# SparkFun_LilyPad-Switched-Battery.net
KiCad netlist of a schematic drawn in EAGLE
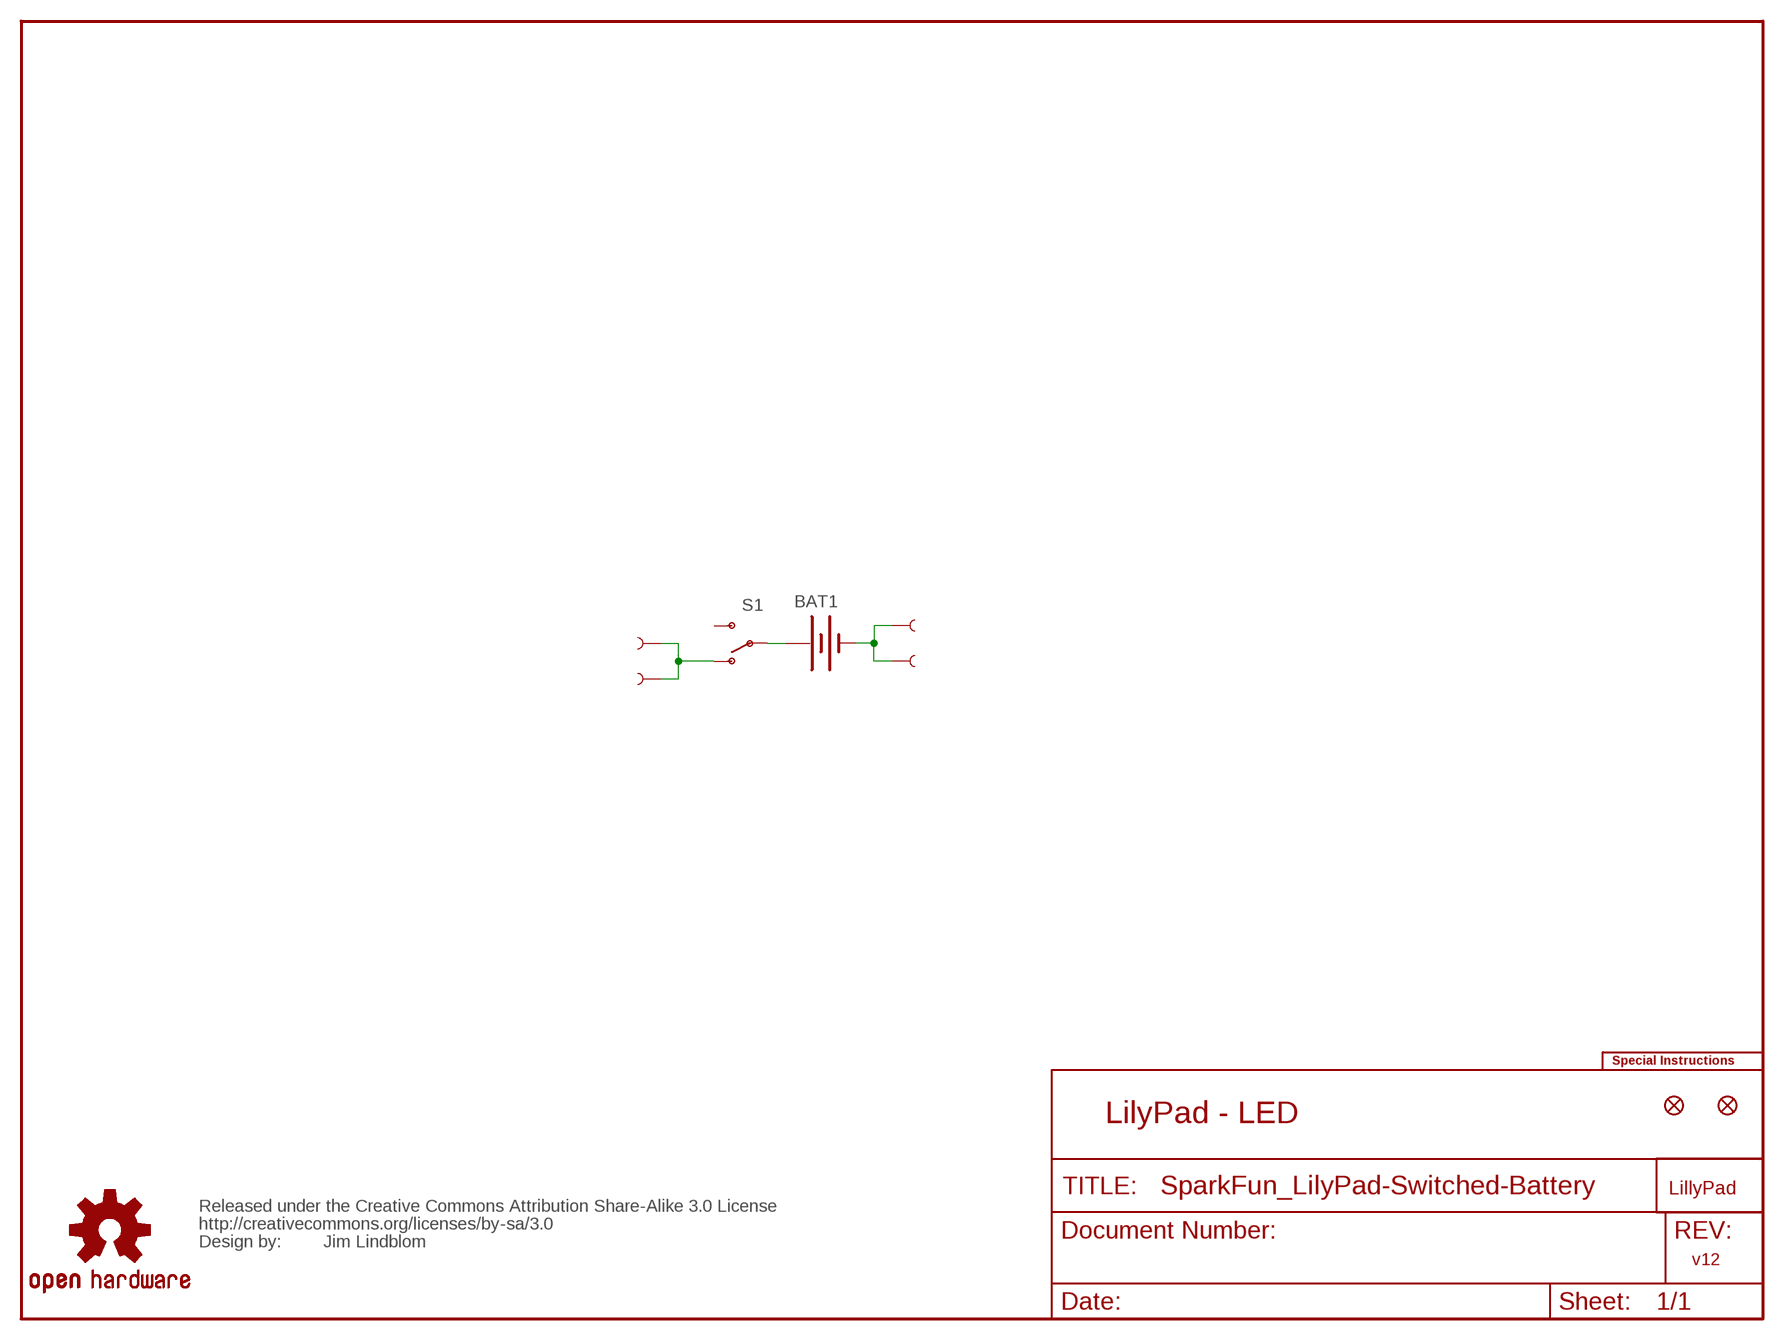
[diagram p0: schematic, sheet 1]

(export (version "E")
  (design (tool "Eeschema 10.0.6"))
  (components
    (comp (ref "BAT1")
      (value "BATTERY20MM_4LEGS")
      (footprint "eagle-import:BATTCON_20MM_4LEGS")
      (libsource (lib "eagle-import") (part "BATTERY20MM_4LEGS"))
    )
    (comp (ref "JP1")
      (value "FIDUCIALUFIDUCIAL")
      (footprint "eagle-import:MICRO-FIDUCIAL")
      (libsource (lib "eagle-import") (part "FIDUCIALUFIDUCIAL"))
    )
    (comp (ref "JP2")
      (value "FIDUCIALUFIDUCIAL")
      (footprint "eagle-import:MICRO-FIDUCIAL")
      (libsource (lib "eagle-import") (part "FIDUCIALUFIDUCIAL"))
    )
    (comp (ref "LOGO1")
      (value "SPECIAL_INSTRUCTIONS-ORDERING")
      (footprint "eagle-import:ORDERING_INSTRUCTIONS")
      (libsource (lib "eagle-import") (part "SPECIAL_INSTRUCTIONS-ORDERING"))
    )
    (comp (ref "S1")
      (value "SWITCH-SPSTSMD")
      (footprint "eagle-import:AYZ0202")
      (libsource (lib "eagle-import") (part "SWITCH-SPSTSMD"))
    )
    (comp (ref "U$1")
      (value "SEWTAP6")
      (footprint "eagle-import:PETAL-SMALL-2SIDE")
      (libsource (lib "eagle-import") (part "SEWTAP6"))
    )
    (comp (ref "U$2")
      (value "SEWTAP6")
      (footprint "eagle-import:PETAL-SMALL-2SIDE")
      (libsource (lib "eagle-import") (part "SEWTAP6"))
    )
    (comp (ref "U$3")
      (value "SEWTAP6")
      (footprint "eagle-import:PETAL-SMALL-2SIDE")
      (libsource (lib "eagle-import") (part "SEWTAP6"))
    )
    (comp (ref "U$4")
      (value "SEWTAP6")
      (footprint "eagle-import:PETAL-SMALL-2SIDE")
      (libsource (lib "eagle-import") (part "SEWTAP6"))
    )
    (comp (ref "U$5")
      (value "LOGO-LPLP")
      (footprint "eagle-import:LOGO-LILYPAD")
      (libsource (lib "eagle-import") (part "LOGO-LPLP"))
    )
    (comp (ref "U$7")
      (value "OSHW-LOGOS")
      (footprint "eagle-import:OSHW-LOGO-S")
      (libsource (lib "eagle-import") (part "OSHW-LOGOS"))
    )
    (comp (ref "U$8")
      (value "CREATIVE_COMMONS")
      (footprint "eagle-import:CREATIVE_COMMONS")
      (libsource (lib "eagle-import") (part "CREATIVE_COMMONS"))
    )
  )
  (nets
    (net (code "1") (name "Net-(BAT1--)") (class "Default")
      (node (ref "BAT1") (pin "2") (pinfunction "-_2") (pintype "power_in"))
      (node (ref "U$1") (pin "1") (pinfunction "1_1") (pintype "bidirectional"))
      (node (ref "U$3") (pin "1") (pinfunction "1_1") (pintype "bidirectional"))
    )
    (net (code "2") (name "Net-(S1-O)") (class "Default")
      (node (ref "S1") (pin "1") (pinfunction "O_1") (pintype "passive"))
      (node (ref "U$2") (pin "1") (pinfunction "1_1") (pintype "bidirectional"))
      (node (ref "U$4") (pin "1") (pinfunction "1_1") (pintype "bidirectional"))
    )
    (net (code "3") (name "Net-(S1-P)") (class "Default")
      (node (ref "BAT1") (pin "1") (pinfunction "+_1") (pintype "power_in"))
      (node (ref "BAT1") (pin "3") (pinfunction "+_3") (pintype "power_in"))
      (node (ref "BAT1") (pin "P$1") (pinfunction "+_P$1") (pintype "power_in"))
      (node (ref "BAT1") (pin "P$2") (pinfunction "+_P$2") (pintype "power_in"))
      (node (ref "S1") (pin "2") (pinfunction "P_2") (pintype "passive"))
    )
    (net (code "4") (name "unconnected-(S1-S-Pad3)") (class "Default")
      (node (ref "S1") (pin "3") (pinfunction "S_3") (pintype "passive"))
    )
  )
)
